# 04_DOWNLOADER.net
KiCad netlist of a schematic drawn in Altium Designer
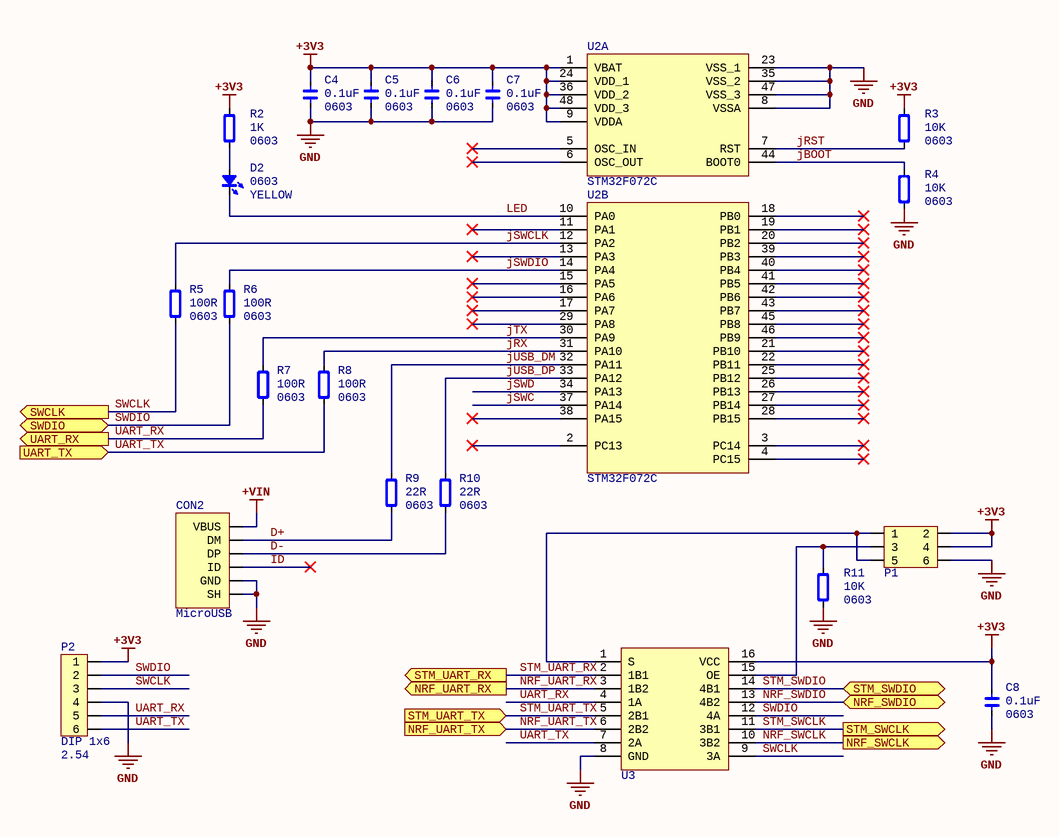
[diagram p0: [04] DOWNLOADER.SchDoc]

(export (version "E")
  (design (tool "Eeschema 10.0.6"))
  (components
    (comp (ref "C4")
      (value "0.1uF")
      (footprint "PCB_PassiveCap:CAP_0603")
      (description "Capacitor")
      (fields (field (name "TYPE") "0603"))
      (libsource (lib "SCH_Passive") (part "Cap_0603"))
    )
    (comp (ref "C5")
      (value "0.1uF")
      (footprint "PCB_PassiveCap:CAP_0603")
      (description "Capacitor")
      (fields (field (name "TYPE") "0603"))
      (libsource (lib "SCH_Passive") (part "Cap_0603"))
    )
    (comp (ref "C6")
      (value "0.1uF")
      (footprint "PCB_PassiveCap:CAP_0603")
      (description "Capacitor")
      (fields (field (name "TYPE") "0603"))
      (libsource (lib "SCH_Passive") (part "Cap_0603"))
    )
    (comp (ref "C7")
      (value "0.1uF")
      (footprint "PCB_PassiveCap:CAP_0603")
      (description "Capacitor")
      (fields (field (name "TYPE") "0603"))
      (libsource (lib "SCH_Passive") (part "Cap_0603"))
    )
    (comp (ref "C8")
      (value "0.1uF")
      (footprint "PCB_PassiveCap:CAP_0603")
      (description "Capacitor")
      (fields (field (name "TYPE") "0603"))
      (libsource (lib "SCH_Passive") (part "Cap_0603"))
    )
    (comp (ref "CON2")
      (value "MicroUSB")
      (footprint "PCB_USB:USB_Micro-AB")
      (description "USB")
      (libsource (lib "SCH_USB") (part "USB_Micro"))
    )
    (comp (ref "D2")
      (value "YELLOW")
      (footprint "PCB_ActiveLED:LED_0603_ORANGE")
      (description "LED")
      (fields (field (name "TYPE") "0603"))
      (libsource (lib "SCH_Active") (part "LED_0603"))
    )
    (comp (ref "P1")
      (value "HDR2x3_2.54")
      (footprint "PCB_ConnectorHDR:HDR2X3_2.54_180")
      (description "Header")
      (libsource (lib "SCH_ConnectorHDR") (part "HDR2x3_2.54"))
    )
    (comp (ref "P2")
      (value "2.54")
      (footprint "PCB_ConnectorHDR:HDR1X6_2.54_180")
      (description "Header")
      (fields (field (name "TYPE") "DIP 1x6") (field (name "Comment") "DIP 1x6"))
      (libsource (lib "SCH_ConnectorHDR") (part "HDR1x6_2.54T"))
    )
    (comp (ref "R2")
      (value "1K")
      (footprint "PCB_PassiveRes:RES_0603")
      (description "Resistor")
      (fields (field (name "TYPE") "0603"))
      (libsource (lib "SCH_Passive") (part "Res_0603"))
    )
    (comp (ref "R3")
      (value "10K")
      (footprint "PCB_PassiveRes:RES_0603")
      (description "Resistor")
      (fields (field (name "TYPE") "0603"))
      (libsource (lib "SCH_Passive") (part "Res_0603"))
    )
    (comp (ref "R4")
      (value "10K")
      (footprint "PCB_PassiveRes:RES_0603")
      (description "Resistor")
      (fields (field (name "TYPE") "0603"))
      (libsource (lib "SCH_Passive") (part "Res_0603"))
    )
    (comp (ref "R5")
      (value "100R")
      (footprint "PCB_PassiveRes:RES_0603")
      (description "Resistor")
      (fields (field (name "TYPE") "0603"))
      (libsource (lib "SCH_Passive") (part "Res_0603"))
    )
    (comp (ref "R6")
      (value "100R")
      (footprint "PCB_PassiveRes:RES_0603")
      (description "Resistor")
      (fields (field (name "TYPE") "0603"))
      (libsource (lib "SCH_Passive") (part "Res_0603"))
    )
    (comp (ref "R7")
      (value "100R")
      (footprint "PCB_PassiveRes:RES_0603")
      (description "Resistor")
      (fields (field (name "TYPE") "0603"))
      (libsource (lib "SCH_Passive") (part "Res_0603"))
    )
    (comp (ref "R8")
      (value "100R")
      (footprint "PCB_PassiveRes:RES_0603")
      (description "Resistor")
      (fields (field (name "TYPE") "0603"))
      (libsource (lib "SCH_Passive") (part "Res_0603"))
    )
    (comp (ref "R9")
      (value "22R")
      (footprint "PCB_PassiveRes:RES_0603")
      (description "Resistor")
      (fields (field (name "TYPE") "0603"))
      (libsource (lib "SCH_Passive") (part "Res_0603"))
    )
    (comp (ref "R10")
      (value "22R")
      (footprint "PCB_PassiveRes:RES_0603")
      (description "Resistor")
      (fields (field (name "TYPE") "0603"))
      (libsource (lib "SCH_Passive") (part "Res_0603"))
    )
    (comp (ref "R11")
      (value "10K")
      (footprint "PCB_PassiveRes:RES_0603")
      (description "Resistor")
      (fields (field (name "TYPE") "0603"))
      (libsource (lib "SCH_Passive") (part "Res_0603"))
    )
    (comp (ref "U2")
      (value "STM32F072C")
      (footprint "PCB_IntegratedCircuit:LQFP_P0.5_48")
      (description "MCU")
      (libsource (lib "SCH_IntegratedCircuit") (part "STM32F103C"))
    )
    (comp (ref "U3")
      (value "SN74CB3Q3257")
      (footprint "PCB_IntegratedCircuit:TSSOP_E170_P0.65_16")
      (description "Switch")
      (libsource (lib "SCH_IntegratedCircuit") (part "SN74CB3Q3257"))
    )
  )
  (nets
    (net (code "1") (name "+3V3") (class "Default")
      (node (ref "C4") (pin "2") (pinfunction "2_2") (pintype "passive"))
      (node (ref "C5") (pin "2") (pinfunction "2_2") (pintype "passive"))
      (node (ref "C6") (pin "2") (pinfunction "2_2") (pintype "passive"))
      (node (ref "C7") (pin "2") (pinfunction "2_2") (pintype "passive"))
      (node (ref "C8") (pin "2") (pinfunction "2_2") (pintype "passive"))
      (node (ref "P1") (pin "2") (pinfunction "2_2") (pintype "passive"))
      (node (ref "P1") (pin "4") (pinfunction "4_4") (pintype "passive"))
      (node (ref "P2") (pin "1") (pinfunction "1_1") (pintype "passive"))
      (node (ref "R2") (pin "2") (pinfunction "2_2") (pintype "passive"))
      (node (ref "R3") (pin "2") (pinfunction "2_2") (pintype "passive"))
      (node (ref "U2") (pin "1") (pinfunction "VBAT_1") (pintype "passive"))
      (node (ref "U2") (pin "24") (pinfunction "VDD_1_24") (pintype "passive"))
      (node (ref "U2") (pin "36") (pinfunction "VDD_2_36") (pintype "passive"))
      (node (ref "U2") (pin "48") (pinfunction "VDD_3_48") (pintype "passive"))
      (node (ref "U2") (pin "9") (pinfunction "VDDA_9") (pintype "passive"))
      (node (ref "U3") (pin "16") (pinfunction "VCC_16") (pintype "passive"))
    )
    (net (code "2") (name "+VIN") (class "Default")
      (node (ref "CON2") (pin "1") (pinfunction "VBUS_1") (pintype "passive"))
    )
    (net (code "3") (name "/D+") (class "Default")
      (node (ref "CON2") (pin "2") (pinfunction "DM_2") (pintype "passive"))
      (node (ref "R9") (pin "1") (pinfunction "1_1") (pintype "passive"))
    )
    (net (code "4") (name "/D-") (class "Default")
      (node (ref "CON2") (pin "3") (pinfunction "DP_3") (pintype "passive"))
      (node (ref "R10") (pin "1") (pinfunction "1_1") (pintype "passive"))
    )
    (net (code "5") (name "/ID") (class "Default")
      (node (ref "CON2") (pin "4") (pinfunction "ID_4") (pintype "passive+no_connect"))
    )
    (net (code "6") (name "/LED") (class "Default")
      (node (ref "D2") (pin "2") (pinfunction "K_2") (pintype "passive"))
      (node (ref "U2") (pin "10") (pinfunction "PA0_10") (pintype "passive"))
    )
    (net (code "7") (name "/NRF_SWCLK") (class "Default")
      (node (ref "U3") (pin "10") (pinfunction "3B2_10") (pintype "passive"))
    )
    (net (code "8") (name "/NRF_SWDIO") (class "Default")
      (node (ref "U3") (pin "13") (pinfunction "4B2_13") (pintype "passive"))
    )
    (net (code "9") (name "/NRF_UART_RX") (class "Default")
      (node (ref "U3") (pin "3") (pinfunction "1B2_3") (pintype "passive"))
    )
    (net (code "10") (name "/NRF_UART_TX") (class "Default")
      (node (ref "U3") (pin "6") (pinfunction "2B2_6") (pintype "passive"))
    )
    (net (code "11") (name "/STM_SWCLK") (class "Default")
      (node (ref "U3") (pin "11") (pinfunction "3B1_11") (pintype "passive"))
    )
    (net (code "12") (name "/STM_SWDIO") (class "Default")
      (node (ref "U3") (pin "14") (pinfunction "4B1_14") (pintype "passive"))
    )
    (net (code "13") (name "/STM_UART_RX") (class "Default")
      (node (ref "U3") (pin "2") (pinfunction "1B1_2") (pintype "passive"))
    )
    (net (code "14") (name "/STM_UART_TX") (class "Default")
      (node (ref "U3") (pin "5") (pinfunction "2B1_5") (pintype "passive"))
    )
    (net (code "15") (name "/SWCLK") (class "Default")
      (node (ref "P2") (pin "3") (pinfunction "3_3") (pintype "passive"))
      (node (ref "R5") (pin "2") (pinfunction "2_2") (pintype "passive"))
      (node (ref "U3") (pin "9") (pinfunction "3A_9") (pintype "passive"))
    )
    (net (code "16") (name "/SWDIO") (class "Default")
      (node (ref "P2") (pin "2") (pinfunction "2_2") (pintype "passive"))
      (node (ref "R6") (pin "2") (pinfunction "2_2") (pintype "passive"))
      (node (ref "U3") (pin "12") (pinfunction "4A_12") (pintype "passive"))
    )
    (net (code "17") (name "/UART_RX") (class "Default")
      (node (ref "P2") (pin "5") (pinfunction "5_5") (pintype "passive"))
      (node (ref "R7") (pin "2") (pinfunction "2_2") (pintype "passive"))
      (node (ref "U3") (pin "4") (pinfunction "1A_4") (pintype "passive"))
    )
    (net (code "18") (name "/UART_TX") (class "Default")
      (node (ref "P2") (pin "6") (pinfunction "6_6") (pintype "passive"))
      (node (ref "R8") (pin "2") (pinfunction "2_2") (pintype "passive"))
      (node (ref "U3") (pin "7") (pinfunction "2A_7") (pintype "passive"))
    )
    (net (code "19") (name "/jBOOT") (class "Default")
      (node (ref "R4") (pin "2") (pinfunction "2_2") (pintype "passive"))
      (node (ref "U2") (pin "44") (pinfunction "BOOT0_44") (pintype "passive"))
    )
    (net (code "20") (name "/jRST") (class "Default")
      (node (ref "R3") (pin "1") (pinfunction "1_1") (pintype "passive"))
      (node (ref "U2") (pin "7") (pinfunction "RST_7") (pintype "passive"))
    )
    (net (code "21") (name "/jRX") (class "Default")
      (node (ref "R8") (pin "1") (pinfunction "1_1") (pintype "passive"))
      (node (ref "U2") (pin "31") (pinfunction "PA10_31") (pintype "passive"))
    )
    (net (code "22") (name "/jSWC") (class "Default")
      (node (ref "U2") (pin "37") (pinfunction "PA14_37") (pintype "passive"))
    )
    (net (code "23") (name "/jSWCLK") (class "Default")
      (node (ref "R5") (pin "1") (pinfunction "1_1") (pintype "passive"))
      (node (ref "U2") (pin "12") (pinfunction "PA2_12") (pintype "passive"))
    )
    (net (code "24") (name "/jSWD") (class "Default")
      (node (ref "U2") (pin "34") (pinfunction "PA13_34") (pintype "passive"))
    )
    (net (code "25") (name "/jSWDIO") (class "Default")
      (node (ref "R6") (pin "1") (pinfunction "1_1") (pintype "passive"))
      (node (ref "U2") (pin "14") (pinfunction "PA4_14") (pintype "passive"))
    )
    (net (code "26") (name "/jTX") (class "Default")
      (node (ref "R7") (pin "1") (pinfunction "1_1") (pintype "passive"))
      (node (ref "U2") (pin "30") (pinfunction "PA9_30") (pintype "passive"))
    )
    (net (code "27") (name "/jUSB_DM") (class "Default")
      (node (ref "R9") (pin "2") (pinfunction "2_2") (pintype "passive"))
      (node (ref "U2") (pin "32") (pinfunction "PA11_32") (pintype "passive"))
    )
    (net (code "28") (name "/jUSB_DP") (class "Default")
      (node (ref "R10") (pin "2") (pinfunction "2_2") (pintype "passive"))
      (node (ref "U2") (pin "33") (pinfunction "PA12_33") (pintype "passive"))
    )
    (net (code "29") (name "GND") (class "Default")
      (node (ref "C4") (pin "1") (pinfunction "1_1") (pintype "passive"))
      (node (ref "C5") (pin "1") (pinfunction "1_1") (pintype "passive"))
      (node (ref "C6") (pin "1") (pinfunction "1_1") (pintype "passive"))
      (node (ref "C7") (pin "1") (pinfunction "1_1") (pintype "passive"))
      (node (ref "C8") (pin "1") (pinfunction "1_1") (pintype "passive"))
      (node (ref "CON2") (pin "0") (pinfunction "SH_0") (pintype "passive"))
      (node (ref "CON2") (pin "5") (pinfunction "GND_5") (pintype "passive"))
      (node (ref "P1") (pin "6") (pinfunction "6_6") (pintype "passive"))
      (node (ref "P2") (pin "4") (pinfunction "4_4") (pintype "passive"))
      (node (ref "R11") (pin "1") (pinfunction "1_1") (pintype "passive"))
      (node (ref "R4") (pin "1") (pinfunction "1_1") (pintype "passive"))
      (node (ref "U2") (pin "23") (pinfunction "VSS_1_23") (pintype "passive"))
      (node (ref "U2") (pin "35") (pinfunction "VSS_2_35") (pintype "passive"))
      (node (ref "U2") (pin "47") (pinfunction "VSS_3_47") (pintype "passive"))
      (node (ref "U2") (pin "8") (pinfunction "VSSA_8") (pintype "passive"))
      (node (ref "U3") (pin "8") (pinfunction "GND_8") (pintype "passive"))
    )
    (net (code "30") (name "Net-(D2-A)") (class "Default")
      (node (ref "D2") (pin "1") (pinfunction "A_1") (pintype "passive"))
      (node (ref "R2") (pin "1") (pinfunction "1_1") (pintype "passive"))
    )
    (net (code "31") (name "Net-(U3-OE)") (class "Default")
      (node (ref "P1") (pin "3") (pinfunction "3_3") (pintype "passive"))
      (node (ref "R11") (pin "2") (pinfunction "2_2") (pintype "passive"))
      (node (ref "U3") (pin "15") (pinfunction "OE_15") (pintype "passive"))
    )
    (net (code "32") (name "Net-(U3-S)") (class "Default")
      (node (ref "P1") (pin "1") (pinfunction "1_1") (pintype "passive"))
      (node (ref "P1") (pin "5") (pinfunction "5_5") (pintype "passive"))
      (node (ref "U3") (pin "1") (pinfunction "S_1") (pintype "passive"))
    )
    (net (code "33") (name "unconnected-(U2A-OSC_IN-Pad5)") (class "Default")
      (node (ref "U2") (pin "5") (pinfunction "OSC_IN_5") (pintype "passive+no_connect"))
    )
    (net (code "34") (name "unconnected-(U2A-OSC_OUT-Pad6)") (class "Default")
      (node (ref "U2") (pin "6") (pinfunction "OSC_OUT_6") (pintype "passive+no_connect"))
    )
    (net (code "35") (name "unconnected-(U2B-PA1-Pad11)") (class "Default")
      (node (ref "U2") (pin "11") (pinfunction "PA1_11") (pintype "passive+no_connect"))
    )
    (net (code "36") (name "unconnected-(U2B-PA3-Pad13)") (class "Default")
      (node (ref "U2") (pin "13") (pinfunction "PA3_13") (pintype "passive+no_connect"))
    )
    (net (code "37") (name "unconnected-(U2B-PA5-Pad15)") (class "Default")
      (node (ref "U2") (pin "15") (pinfunction "PA5_15") (pintype "passive+no_connect"))
    )
    (net (code "38") (name "unconnected-(U2B-PA6-Pad16)") (class "Default")
      (node (ref "U2") (pin "16") (pinfunction "PA6_16") (pintype "passive+no_connect"))
    )
    (net (code "39") (name "unconnected-(U2B-PA7-Pad17)") (class "Default")
      (node (ref "U2") (pin "17") (pinfunction "PA7_17") (pintype "passive+no_connect"))
    )
    (net (code "40") (name "unconnected-(U2B-PA8-Pad29)") (class "Default")
      (node (ref "U2") (pin "29") (pinfunction "PA8_29") (pintype "passive+no_connect"))
    )
    (net (code "41") (name "unconnected-(U2B-PA15-Pad38)") (class "Default")
      (node (ref "U2") (pin "38") (pinfunction "PA15_38") (pintype "passive+no_connect"))
    )
    (net (code "42") (name "unconnected-(U2B-PB0-Pad18)") (class "Default")
      (node (ref "U2") (pin "18") (pinfunction "PB0_18") (pintype "passive+no_connect"))
    )
    (net (code "43") (name "unconnected-(U2B-PB1-Pad19)") (class "Default")
      (node (ref "U2") (pin "19") (pinfunction "PB1_19") (pintype "passive+no_connect"))
    )
    (net (code "44") (name "unconnected-(U2B-PB2-Pad20)") (class "Default")
      (node (ref "U2") (pin "20") (pinfunction "PB2_20") (pintype "passive+no_connect"))
    )
    (net (code "45") (name "unconnected-(U2B-PB3-Pad39)") (class "Default")
      (node (ref "U2") (pin "39") (pinfunction "PB3_39") (pintype "passive+no_connect"))
    )
    (net (code "46") (name "unconnected-(U2B-PB4-Pad40)") (class "Default")
      (node (ref "U2") (pin "40") (pinfunction "PB4_40") (pintype "passive+no_connect"))
    )
    (net (code "47") (name "unconnected-(U2B-PB5-Pad41)") (class "Default")
      (node (ref "U2") (pin "41") (pinfunction "PB5_41") (pintype "passive+no_connect"))
    )
    (net (code "48") (name "unconnected-(U2B-PB6-Pad42)") (class "Default")
      (node (ref "U2") (pin "42") (pinfunction "PB6_42") (pintype "passive+no_connect"))
    )
    (net (code "49") (name "unconnected-(U2B-PB7-Pad43)") (class "Default")
      (node (ref "U2") (pin "43") (pinfunction "PB7_43") (pintype "passive+no_connect"))
    )
    (net (code "50") (name "unconnected-(U2B-PB8-Pad45)") (class "Default")
      (node (ref "U2") (pin "45") (pinfunction "PB8_45") (pintype "passive+no_connect"))
    )
    (net (code "51") (name "unconnected-(U2B-PB9-Pad46)") (class "Default")
      (node (ref "U2") (pin "46") (pinfunction "PB9_46") (pintype "passive+no_connect"))
    )
    (net (code "52") (name "unconnected-(U2B-PB10-Pad21)") (class "Default")
      (node (ref "U2") (pin "21") (pinfunction "PB10_21") (pintype "passive+no_connect"))
    )
    (net (code "53") (name "unconnected-(U2B-PB11-Pad22)") (class "Default")
      (node (ref "U2") (pin "22") (pinfunction "PB11_22") (pintype "passive+no_connect"))
    )
    (net (code "54") (name "unconnected-(U2B-PB12-Pad25)") (class "Default")
      (node (ref "U2") (pin "25") (pinfunction "PB12_25") (pintype "passive+no_connect"))
    )
    (net (code "55") (name "unconnected-(U2B-PB13-Pad26)") (class "Default")
      (node (ref "U2") (pin "26") (pinfunction "PB13_26") (pintype "passive+no_connect"))
    )
    (net (code "56") (name "unconnected-(U2B-PB14-Pad27)") (class "Default")
      (node (ref "U2") (pin "27") (pinfunction "PB14_27") (pintype "passive+no_connect"))
    )
    (net (code "57") (name "unconnected-(U2B-PB15-Pad28)") (class "Default")
      (node (ref "U2") (pin "28") (pinfunction "PB15_28") (pintype "passive+no_connect"))
    )
    (net (code "58") (name "unconnected-(U2B-PC13-Pad2)") (class "Default")
      (node (ref "U2") (pin "2") (pinfunction "PC13_2") (pintype "passive+no_connect"))
    )
    (net (code "59") (name "unconnected-(U2B-PC14-Pad3)") (class "Default")
      (node (ref "U2") (pin "3") (pinfunction "PC14_3") (pintype "passive+no_connect"))
    )
    (net (code "60") (name "unconnected-(U2B-PC15-Pad4)") (class "Default")
      (node (ref "U2") (pin "4") (pinfunction "PC15_4") (pintype "passive+no_connect"))
    )
  )
)
